# grizzly_bear.net
KiCad netlist of a schematic drawn in EAGLE
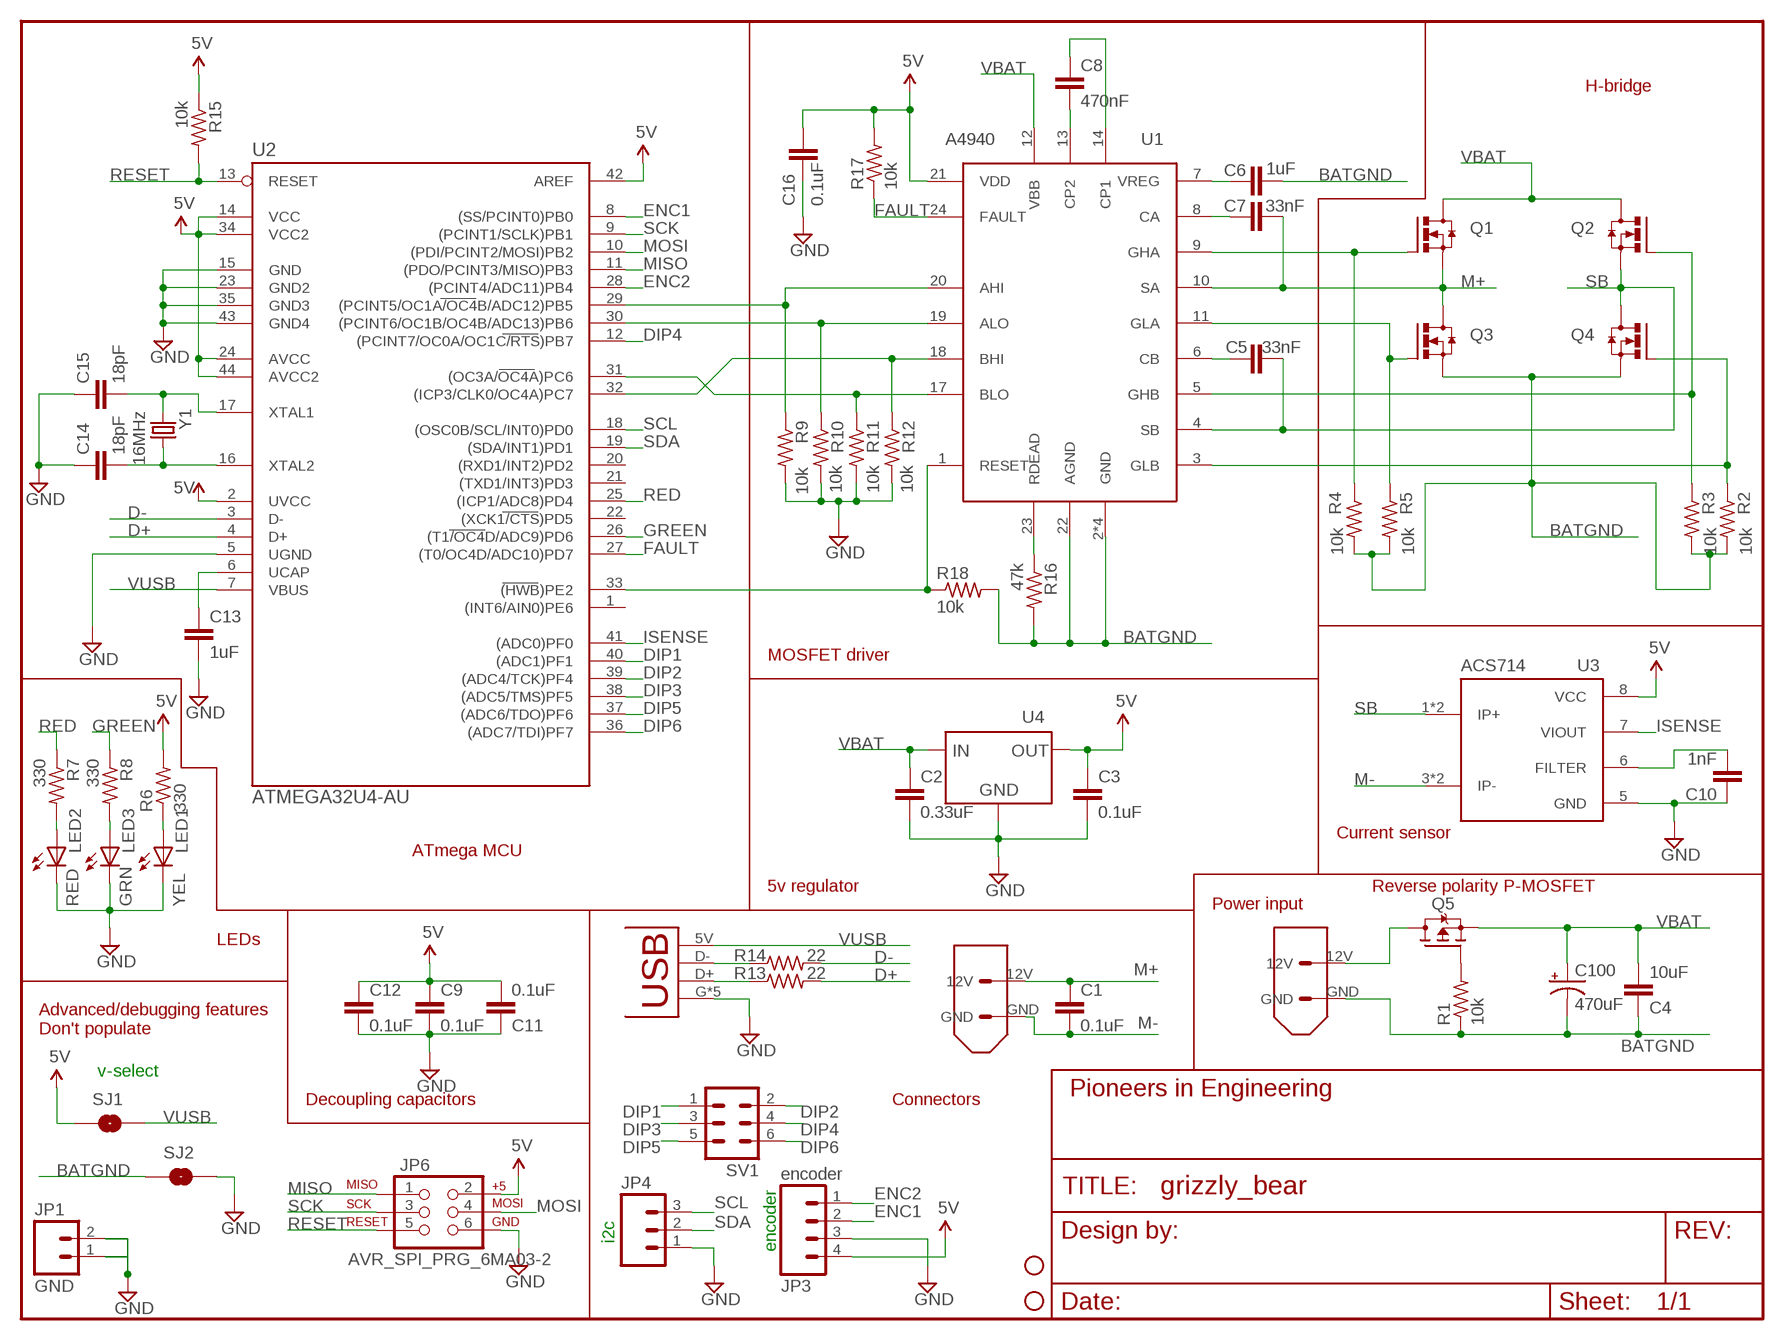
[diagram p0: schematic, sheet 1]

(export (version "E")
  (design (tool "Eeschema 10.0.6"))
  (components
    (comp (ref "C1")
      (value "0.1uF")
      (footprint "eagle-import:0603-CAP")
      (libsource (lib "eagle-import") (part "CAP0603-CAP"))
    )
    (comp (ref "C2")
      (value "0.33uF")
      (footprint "eagle-import:0603-CAP")
      (libsource (lib "eagle-import") (part "CAP0603-CAP"))
    )
    (comp (ref "C3")
      (value "0.1uF")
      (footprint "eagle-import:0603-CAP")
      (libsource (lib "eagle-import") (part "CAP0603-CAP"))
    )
    (comp (ref "C4")
      (value "10uF")
      (footprint "eagle-import:0603-CAP")
      (libsource (lib "eagle-import") (part "CAP0603-CAP"))
    )
    (comp (ref "C5")
      (value "33nF")
      (footprint "eagle-import:0603-CAP")
      (libsource (lib "eagle-import") (part "CAP0603-CAP"))
    )
    (comp (ref "C6")
      (value "1uF")
      (footprint "eagle-import:0603-CAP")
      (libsource (lib "eagle-import") (part "CAP0603-CAP"))
    )
    (comp (ref "C7")
      (value "33nF")
      (footprint "eagle-import:0603-CAP")
      (libsource (lib "eagle-import") (part "CAP0603-CAP"))
    )
    (comp (ref "C8")
      (value "470nF")
      (footprint "eagle-import:0603-CAP")
      (libsource (lib "eagle-import") (part "CAP0603-CAP"))
    )
    (comp (ref "C9")
      (value "0.1uF")
      (footprint "eagle-import:0603-CAP")
      (libsource (lib "eagle-import") (part "CAP0603-CAP"))
    )
    (comp (ref "C10")
      (value "1nF")
      (footprint "eagle-import:0603-CAP")
      (libsource (lib "eagle-import") (part "CAP0603-CAP"))
    )
    (comp (ref "C11")
      (value "0.1uF")
      (footprint "eagle-import:0603-CAP")
      (libsource (lib "eagle-import") (part "CAP0603-CAP"))
    )
    (comp (ref "C12")
      (value "0.1uF")
      (footprint "eagle-import:0603-CAP")
      (libsource (lib "eagle-import") (part "CAP0603-CAP"))
    )
    (comp (ref "C13")
      (value "1uF")
      (footprint "eagle-import:0603-CAP")
      (libsource (lib "eagle-import") (part "CAP0603-CAP"))
    )
    (comp (ref "C14")
      (value "18pF")
      (footprint "eagle-import:0603-CAP")
      (libsource (lib "eagle-import") (part "CAP0603-CAP"))
    )
    (comp (ref "C15")
      (value "18pF")
      (footprint "eagle-import:0603-CAP")
      (libsource (lib "eagle-import") (part "CAP0603-CAP"))
    )
    (comp (ref "C16")
      (value "0.1uF")
      (footprint "eagle-import:0603-CAP")
      (libsource (lib "eagle-import") (part "CAP0603-CAP"))
    )
    (comp (ref "C100")
      (value "470uF")
      (footprint "eagle-import:PANASONIC_G")
      (libsource (lib "eagle-import") (part "CAP_POLG"))
    )
    (comp (ref "JP1")
      (value "GND")
      (footprint "eagle-import:1X02")
      (libsource (lib "eagle-import") (part "M02PTH"))
    )
    (comp (ref "JP3")
      (value "encoder")
      (footprint "eagle-import:1X04-MTA")
      (fields (field (name "PARTNUMBER") "A1922-ND"))
      (libsource (lib "eagle-import") (part "M041X04-MTA"))
    )
    (comp (ref "JP4")
      (value "M031X03-MTA")
      (footprint "eagle-import:1X03-MTA")
      (fields (field (name "PARTNUMBER") "A19470-ND"))
      (libsource (lib "eagle-import") (part "M031X03-MTA"))
    )
    (comp (ref "JP6")
      (value "AVR_SPI_PRG_6MA03-2")
      (footprint "eagle-import:MA03-2")
      (libsource (lib "eagle-import") (part "AVR_SPI_PRG_6MA03-2"))
    )
    (comp (ref "LED1")
      (value "YEL")
      (footprint "eagle-import:LED-0805")
      (libsource (lib "eagle-import") (part "LED0805"))
    )
    (comp (ref "LED2")
      (value "RED")
      (footprint "eagle-import:LED-0805")
      (libsource (lib "eagle-import") (part "LED0805"))
    )
    (comp (ref "LED3")
      (value "GRN")
      (footprint "eagle-import:LED-0805")
      (libsource (lib "eagle-import") (part "LED0805"))
    )
    (comp (ref "Q1")
      (value "N-CHANNEL-MOSFET")
      (footprint "eagle-import:SOT669")
      (libsource (lib "eagle-import") (part "N-CHANNEL-MOSFET"))
    )
    (comp (ref "Q2")
      (value "N-CHANNEL-MOSFET")
      (footprint "eagle-import:SOT669")
      (libsource (lib "eagle-import") (part "N-CHANNEL-MOSFET"))
    )
    (comp (ref "Q3")
      (value "N-CHANNEL-MOSFET")
      (footprint "eagle-import:SOT669")
      (libsource (lib "eagle-import") (part "N-CHANNEL-MOSFET"))
    )
    (comp (ref "Q4")
      (value "N-CHANNEL-MOSFET")
      (footprint "eagle-import:SOT669")
      (libsource (lib "eagle-import") (part "N-CHANNEL-MOSFET"))
    )
    (comp (ref "Q5")
      (value "IPD90P03P4L")
      (footprint "eagle-import:TO252")
      (libsource (lib "eagle-import") (part "P-CHANNEL-MOSFETTO252"))
    )
    (comp (ref "R1")
      (value "10k")
      (footprint "eagle-import:R0603")
      (libsource (lib "eagle-import") (part "R-US_R0603"))
    )
    (comp (ref "R2")
      (value "10k")
      (footprint "eagle-import:R0603")
      (libsource (lib "eagle-import") (part "R-US_R0603"))
    )
    (comp (ref "R3")
      (value "10k")
      (footprint "eagle-import:R0603")
      (libsource (lib "eagle-import") (part "R-US_R0603"))
    )
    (comp (ref "R4")
      (value "10k")
      (footprint "eagle-import:R0603")
      (libsource (lib "eagle-import") (part "R-US_R0603"))
    )
    (comp (ref "R5")
      (value "10k")
      (footprint "eagle-import:R0603")
      (libsource (lib "eagle-import") (part "R-US_R0603"))
    )
    (comp (ref "R6")
      (value "330")
      (footprint "eagle-import:R0603")
      (libsource (lib "eagle-import") (part "R-US_R0603"))
    )
    (comp (ref "R7")
      (value "330")
      (footprint "eagle-import:R0603")
      (libsource (lib "eagle-import") (part "R-US_R0603"))
    )
    (comp (ref "R8")
      (value "330")
      (footprint "eagle-import:R0603")
      (libsource (lib "eagle-import") (part "R-US_R0603"))
    )
    (comp (ref "R9")
      (value "10k")
      (footprint "eagle-import:R0603")
      (libsource (lib "eagle-import") (part "R-US_R0603"))
    )
    (comp (ref "R10")
      (value "10k")
      (footprint "eagle-import:R0603")
      (libsource (lib "eagle-import") (part "R-US_R0603"))
    )
    (comp (ref "R11")
      (value "10k")
      (footprint "eagle-import:R0603")
      (libsource (lib "eagle-import") (part "R-US_R0603"))
    )
    (comp (ref "R12")
      (value "10k")
      (footprint "eagle-import:R0603")
      (libsource (lib "eagle-import") (part "R-US_R0603"))
    )
    (comp (ref "R13")
      (value "22")
      (footprint "eagle-import:R0603")
      (libsource (lib "eagle-import") (part "R-US_R0603"))
    )
    (comp (ref "R14")
      (value "22")
      (footprint "eagle-import:R0603")
      (libsource (lib "eagle-import") (part "R-US_R0603"))
    )
    (comp (ref "R15")
      (value "10k")
      (footprint "eagle-import:R0603")
      (libsource (lib "eagle-import") (part "R-US_R0603"))
    )
    (comp (ref "R16")
      (value "47k")
      (footprint "eagle-import:R0603")
      (libsource (lib "eagle-import") (part "R-US_R0603"))
    )
    (comp (ref "R17")
      (value "10k")
      (footprint "eagle-import:R0603")
      (libsource (lib "eagle-import") (part "R-US_R0603"))
    )
    (comp (ref "R18")
      (value "10k")
      (footprint "eagle-import:R0603")
      (libsource (lib "eagle-import") (part "R-US_R0603"))
    )
    (comp (ref "SJ1")
      (value "SOLDERJUMPERNO")
      (footprint "eagle-import:SJ_2S-NO")
      (libsource (lib "eagle-import") (part "SOLDERJUMPERNO"))
    )
    (comp (ref "SJ2")
      (value "SOLDERJUMPERNO")
      (footprint "eagle-import:SJ_2S-NO")
      (libsource (lib "eagle-import") (part "SOLDERJUMPERNO"))
    )
    (comp (ref "STANDOFF1")
      (value "STAND-OFF")
      (footprint "eagle-import:STAND-OFF")
      (libsource (lib "eagle-import") (part "STAND-OFF"))
    )
    (comp (ref "STANDOFF2")
      (value "STAND-OFF")
      (footprint "eagle-import:STAND-OFF")
      (libsource (lib "eagle-import") (part "STAND-OFF"))
    )
    (comp (ref "SV1")
      (value "MA03-2")
      (footprint "eagle-import:MA03-2")
      (libsource (lib "eagle-import") (part "MA03-2"))
    )
    (comp (ref "U$2")
      (value "USB-M26FTR")
      (footprint "eagle-import:USB-M26FTR")
      (libsource (lib "eagle-import") (part "USB-M26FTR"))
    )
    (comp (ref "U$18")
      (value "XT60CONNECTOR")
      (footprint "eagle-import:XT60CONNECTOR")
      (fields (field (name "PARTNUMBER") "PRT-10474 "))
      (libsource (lib "eagle-import") (part "XT60CONNECTOR"))
    )
    (comp (ref "U$19")
      (value "XT60CONNECTOR")
      (footprint "eagle-import:XT60CONNECTOR")
      (fields (field (name "PARTNUMBER") "PRT-10474 "))
      (libsource (lib "eagle-import") (part "XT60CONNECTOR"))
    )
    (comp (ref "U1")
      (value "A4940")
      (footprint "eagle-import:24-PIN_TSSOP")
      (libsource (lib "eagle-import") (part "A4940"))
    )
    (comp (ref "U2")
      (value "ATMEGA32U4-AU")
      (footprint "eagle-import:TQFP44")
      (libsource (lib "eagle-import") (part "ATMEGA32U4-AU"))
    )
    (comp (ref "U3")
      (value "ACS714")
      (footprint "eagle-import:8-PIN_SOIC")
      (libsource (lib "eagle-import") (part "ACS714"))
    )
    (comp (ref "U4")
      (value "UA78L00")
      (footprint "eagle-import:SOT-89-3")
      (libsource (lib "eagle-import") (part "UA78L00"))
    )
    (comp (ref "Y1")
      (value "16MHz")
      (footprint "eagle-import:HC49UP")
      (libsource (lib "eagle-import") (part "CRYSTALSMD"))
    )
  )
  (nets
    (net (code "1") (name "/BATGND") (class "Default")
      (node (ref "C100") (pin "-") (pinfunction "-_-") (pintype "passive"))
      (node (ref "C4") (pin "1") (pinfunction "1_1") (pintype "passive"))
      (node (ref "C6") (pin "2") (pinfunction "2_2") (pintype "passive"))
      (node (ref "Q3") (pin "1") (pinfunction "S_1") (pintype "passive"))
      (node (ref "Q3") (pin "2") (pinfunction "S_2") (pintype "passive"))
      (node (ref "Q3") (pin "3") (pinfunction "S_3") (pintype "passive"))
      (node (ref "Q4") (pin "1") (pinfunction "S_1") (pintype "passive"))
      (node (ref "Q4") (pin "2") (pinfunction "S_2") (pintype "passive"))
      (node (ref "Q4") (pin "3") (pinfunction "S_3") (pintype "passive"))
      (node (ref "R1") (pin "1") (pinfunction "1_1") (pintype "passive"))
      (node (ref "R16") (pin "2") (pinfunction "2_2") (pintype "passive"))
      (node (ref "R18") (pin "2") (pinfunction "2_2") (pintype "passive"))
      (node (ref "R2") (pin "2") (pinfunction "2_2") (pintype "passive"))
      (node (ref "R3") (pin "2") (pinfunction "2_2") (pintype "passive"))
      (node (ref "R4") (pin "2") (pinfunction "2_2") (pintype "passive"))
      (node (ref "R5") (pin "2") (pinfunction "2_2") (pintype "passive"))
      (node (ref "SJ2") (pin "1") (pinfunction "1_1") (pintype "passive"))
      (node (ref "U$18") (pin "GND") (pinfunction "GND_GND") (pintype "bidirectional"))
      (node (ref "U1") (pin "15") (pinfunction "GND_15") (pintype "bidirectional"))
      (node (ref "U1") (pin "16") (pinfunction "GND_16") (pintype "bidirectional"))
      (node (ref "U1") (pin "2") (pinfunction "GND_2") (pintype "bidirectional"))
      (node (ref "U1") (pin "22") (pinfunction "AGND_22") (pintype "bidirectional"))
      (node (ref "U1") (pin "PAD") (pinfunction "GND_PAD") (pintype "bidirectional"))
    )
    (net (code "2") (name "/D+") (class "Default")
      (node (ref "R13") (pin "2") (pinfunction "2_2") (pintype "passive"))
      (node (ref "U2") (pin "4") (pinfunction "D+_4") (pintype "bidirectional"))
    )
    (net (code "3") (name "/D-") (class "Default")
      (node (ref "R14") (pin "2") (pinfunction "2_2") (pintype "passive"))
      (node (ref "U2") (pin "3") (pinfunction "D-_3") (pintype "bidirectional"))
    )
    (net (code "4") (name "/DIP1") (class "Default")
      (node (ref "SV1") (pin "1") (pinfunction "1_1") (pintype "passive"))
      (node (ref "U2") (pin "40") (pinfunction "(ADC1)PF1_40") (pintype "bidirectional"))
    )
    (net (code "5") (name "/DIP2") (class "Default")
      (node (ref "SV1") (pin "2") (pinfunction "2_2") (pintype "passive"))
      (node (ref "U2") (pin "39") (pinfunction "(ADC4/TCK)PF4_39") (pintype "bidirectional"))
    )
    (net (code "6") (name "/DIP3") (class "Default")
      (node (ref "SV1") (pin "3") (pinfunction "3_3") (pintype "passive"))
      (node (ref "U2") (pin "38") (pinfunction "(ADC5/TMS)PF5_38") (pintype "bidirectional"))
    )
    (net (code "7") (name "/DIP4") (class "Default")
      (node (ref "SV1") (pin "4") (pinfunction "4_4") (pintype "passive"))
      (node (ref "U2") (pin "12") (pinfunction "(PCINT7/OC0A/OC1C/RTS)PB7_12") (pintype "bidirectional"))
    )
    (net (code "8") (name "/DIP5") (class "Default")
      (node (ref "SV1") (pin "5") (pinfunction "5_5") (pintype "passive"))
      (node (ref "U2") (pin "37") (pinfunction "(ADC6/TDO)PF6_37") (pintype "bidirectional"))
    )
    (net (code "9") (name "/DIP6") (class "Default")
      (node (ref "SV1") (pin "6") (pinfunction "6_6") (pintype "passive"))
      (node (ref "U2") (pin "36") (pinfunction "(ADC7/TDI)PF7_36") (pintype "bidirectional"))
    )
    (net (code "10") (name "/ENC1") (class "Default")
      (node (ref "JP3") (pin "2") (pinfunction "2_2") (pintype "passive"))
      (node (ref "U2") (pin "8") (pinfunction "(SS/PCINT0)PB0_8") (pintype "bidirectional"))
    )
    (net (code "11") (name "/ENC2") (class "Default")
      (node (ref "JP3") (pin "1") (pinfunction "1_1") (pintype "passive"))
      (node (ref "U2") (pin "28") (pinfunction "(PCINT4/ADC11)PB4_28") (pintype "bidirectional"))
    )
    (net (code "12") (name "/FAULT") (class "Default")
      (node (ref "R17") (pin "1") (pinfunction "1_1") (pintype "passive"))
      (node (ref "U1") (pin "24") (pinfunction "FAULT_24") (pintype "bidirectional"))
      (node (ref "U2") (pin "27") (pinfunction "(T0/OC4D/ADC10)PD7_27") (pintype "bidirectional"))
    )
    (net (code "13") (name "/GREEN") (class "Default")
      (node (ref "R8") (pin "1") (pinfunction "1_1") (pintype "passive"))
      (node (ref "U2") (pin "26") (pinfunction "(T1/OC4D/ADC9)PD6_26") (pintype "bidirectional"))
    )
    (net (code "14") (name "/ISENSE") (class "Default")
      (node (ref "U2") (pin "41") (pinfunction "(ADC0)PF0_41") (pintype "bidirectional"))
      (node (ref "U3") (pin "7") (pinfunction "VIOUT_7") (pintype "bidirectional"))
    )
    (net (code "15") (name "/M+") (class "Default")
      (node (ref "C1") (pin "1") (pinfunction "1_1") (pintype "passive"))
      (node (ref "C7") (pin "2") (pinfunction "2_2") (pintype "passive"))
      (node (ref "Q1") (pin "1") (pinfunction "S_1") (pintype "passive"))
      (node (ref "Q1") (pin "2") (pinfunction "S_2") (pintype "passive"))
      (node (ref "Q1") (pin "3") (pinfunction "S_3") (pintype "passive"))
      (node (ref "Q3") (pin "MB") (pinfunction "D_MB") (pintype "passive"))
      (node (ref "U$19") (pin "12V") (pinfunction "12V_12V") (pintype "bidirectional"))
      (node (ref "U1") (pin "10") (pinfunction "SA_10") (pintype "bidirectional"))
    )
    (net (code "16") (name "/M-") (class "Default")
      (node (ref "C1") (pin "2") (pinfunction "2_2") (pintype "passive"))
      (node (ref "U$19") (pin "GND") (pinfunction "GND_GND") (pintype "bidirectional"))
      (node (ref "U3") (pin "3") (pinfunction "IP-_3") (pintype "bidirectional"))
      (node (ref "U3") (pin "4") (pinfunction "IP-_4") (pintype "bidirectional"))
    )
    (net (code "17") (name "/MISO") (class "Default")
      (node (ref "JP6") (pin "1") (pinfunction "1_1") (pintype "passive"))
      (node (ref "U2") (pin "11") (pinfunction "(PDO/PCINT3/MISO)PB3_11") (pintype "bidirectional"))
    )
    (net (code "18") (name "/MOSI") (class "Default")
      (node (ref "JP6") (pin "4") (pinfunction "4_4") (pintype "passive"))
      (node (ref "U2") (pin "10") (pinfunction "(PDI/PCINT2/MOSI)PB2_10") (pintype "bidirectional"))
    )
    (net (code "19") (name "/RED") (class "Default")
      (node (ref "R7") (pin "1") (pinfunction "1_1") (pintype "passive"))
      (node (ref "U2") (pin "25") (pinfunction "(ICP1/ADC8)PD4_25") (pintype "bidirectional"))
    )
    (net (code "20") (name "/RESET") (class "Default")
      (node (ref "JP6") (pin "5") (pinfunction "5_5") (pintype "passive"))
      (node (ref "R15") (pin "2") (pinfunction "2_2") (pintype "passive"))
      (node (ref "U2") (pin "13") (pinfunction "RESET_13") (pintype "bidirectional"))
    )
    (net (code "21") (name "/SB") (class "Default")
      (node (ref "C5") (pin "1") (pinfunction "1_1") (pintype "passive"))
      (node (ref "Q2") (pin "1") (pinfunction "S_1") (pintype "passive"))
      (node (ref "Q2") (pin "2") (pinfunction "S_2") (pintype "passive"))
      (node (ref "Q2") (pin "3") (pinfunction "S_3") (pintype "passive"))
      (node (ref "Q4") (pin "MB") (pinfunction "D_MB") (pintype "passive"))
      (node (ref "U1") (pin "4") (pinfunction "SB_4") (pintype "bidirectional"))
      (node (ref "U3") (pin "1") (pinfunction "IP+_1") (pintype "bidirectional"))
      (node (ref "U3") (pin "2") (pinfunction "IP+_2") (pintype "bidirectional"))
    )
    (net (code "22") (name "/SCK") (class "Default")
      (node (ref "JP6") (pin "3") (pinfunction "3_3") (pintype "passive"))
      (node (ref "U2") (pin "9") (pinfunction "(PCINT1/SCLK)PB1_9") (pintype "bidirectional"))
    )
    (net (code "23") (name "/SCL") (class "Default")
      (node (ref "JP4") (pin "3") (pinfunction "3_3") (pintype "passive"))
      (node (ref "U2") (pin "18") (pinfunction "(OSC0B/SCL/INT0)PD0_18") (pintype "bidirectional"))
    )
    (net (code "24") (name "/SDA") (class "Default")
      (node (ref "JP4") (pin "2") (pinfunction "2_2") (pintype "passive"))
      (node (ref "U2") (pin "19") (pinfunction "(SDA/INT1)PD1_19") (pintype "bidirectional"))
    )
    (net (code "25") (name "/VBAT") (class "Default")
      (node (ref "C100") (pin "+") (pinfunction "+_+") (pintype "passive"))
      (node (ref "C2") (pin "1") (pinfunction "1_1") (pintype "passive"))
      (node (ref "C4") (pin "2") (pinfunction "2_2") (pintype "passive"))
      (node (ref "Q1") (pin "MB") (pinfunction "D_MB") (pintype "passive"))
      (node (ref "Q2") (pin "MB") (pinfunction "D_MB") (pintype "passive"))
      (node (ref "Q5") (pin "2") (pinfunction "S_2") (pintype "passive"))
      (node (ref "U1") (pin "12") (pinfunction "VBB_12") (pintype "bidirectional"))
      (node (ref "U4") (pin "INPUT") (pinfunction "IN_INPUT") (pintype "bidirectional"))
    )
    (net (code "26") (name "/VUSB") (class "Default")
      (node (ref "SJ1") (pin "2") (pinfunction "2_2") (pintype "passive"))
      (node (ref "U$2") (pin "5V") (pinfunction "5V_5V") (pintype "bidirectional"))
      (node (ref "U2") (pin "7") (pinfunction "VBUS_7") (pintype "bidirectional"))
    )
    (net (code "27") (name "5V") (class "Default")
      (node (ref "C11") (pin "2") (pinfunction "2_2") (pintype "passive"))
      (node (ref "C12") (pin "1") (pinfunction "1_1") (pintype "passive"))
      (node (ref "C16") (pin "1") (pinfunction "1_1") (pintype "passive"))
      (node (ref "C3") (pin "1") (pinfunction "1_1") (pintype "passive"))
      (node (ref "C9") (pin "1") (pinfunction "1_1") (pintype "passive"))
      (node (ref "JP3") (pin "4") (pinfunction "4_4") (pintype "passive"))
      (node (ref "JP6") (pin "2") (pinfunction "2_2") (pintype "passive"))
      (node (ref "R15") (pin "1") (pinfunction "1_1") (pintype "passive"))
      (node (ref "R17") (pin "2") (pinfunction "2_2") (pintype "passive"))
      (node (ref "R6") (pin "2") (pinfunction "2_2") (pintype "passive"))
      (node (ref "SJ1") (pin "1") (pinfunction "1_1") (pintype "passive"))
      (node (ref "U1") (pin "21") (pinfunction "VDD_21") (pintype "bidirectional"))
      (node (ref "U2") (pin "14") (pinfunction "VCC_14") (pintype "bidirectional"))
      (node (ref "U2") (pin "2") (pinfunction "UVCC_2") (pintype "bidirectional"))
      (node (ref "U2") (pin "24") (pinfunction "AVCC_24") (pintype "bidirectional"))
      (node (ref "U2") (pin "34") (pinfunction "VCC2_34") (pintype "bidirectional"))
      (node (ref "U2") (pin "42") (pinfunction "AREF_42") (pintype "bidirectional"))
      (node (ref "U2") (pin "44") (pinfunction "AVCC2_44") (pintype "bidirectional"))
      (node (ref "U3") (pin "8") (pinfunction "VCC_8") (pintype "bidirectional"))
      (node (ref "U4") (pin "OUTPUT") (pinfunction "OUT_OUTPUT") (pintype "bidirectional"))
    )
    (net (code "28") (name "GND") (class "Default")
      (node (ref "C10") (pin "1") (pinfunction "1_1") (pintype "passive"))
      (node (ref "C11") (pin "1") (pinfunction "1_1") (pintype "passive"))
      (node (ref "C12") (pin "2") (pinfunction "2_2") (pintype "passive"))
      (node (ref "C13") (pin "2") (pinfunction "2_2") (pintype "passive"))
      (node (ref "C14") (pin "1") (pinfunction "1_1") (pintype "passive"))
      (node (ref "C15") (pin "1") (pinfunction "1_1") (pintype "passive"))
      (node (ref "C16") (pin "2") (pinfunction "2_2") (pintype "passive"))
      (node (ref "C2") (pin "2") (pinfunction "2_2") (pintype "passive"))
      (node (ref "C3") (pin "2") (pinfunction "2_2") (pintype "passive"))
      (node (ref "C9") (pin "2") (pinfunction "2_2") (pintype "passive"))
      (node (ref "JP1") (pin "1") (pinfunction "1_1") (pintype "passive"))
      (node (ref "JP1") (pin "2") (pinfunction "2_2") (pintype "passive"))
      (node (ref "JP3") (pin "3") (pinfunction "3_3") (pintype "passive"))
      (node (ref "JP4") (pin "1") (pinfunction "1_1") (pintype "passive"))
      (node (ref "JP6") (pin "6") (pinfunction "6_6") (pintype "passive"))
      (node (ref "LED1") (pin "C") (pinfunction "C_C") (pintype "passive"))
      (node (ref "LED2") (pin "C") (pinfunction "C_C") (pintype "passive"))
      (node (ref "LED3") (pin "C") (pinfunction "C_C") (pintype "passive"))
      (node (ref "R10") (pin "2") (pinfunction "2_2") (pintype "passive"))
      (node (ref "R11") (pin "2") (pinfunction "2_2") (pintype "passive"))
      (node (ref "R12") (pin "2") (pinfunction "2_2") (pintype "passive"))
      (node (ref "R9") (pin "2") (pinfunction "2_2") (pintype "passive"))
      (node (ref "SJ2") (pin "2") (pinfunction "2_2") (pintype "passive"))
      (node (ref "U$2") (pin "G") (pinfunction "G_G") (pintype "bidirectional"))
      (node (ref "U$2") (pin "S1") (pinfunction "G_S1") (pintype "bidirectional"))
      (node (ref "U$2") (pin "S2") (pinfunction "G_S2") (pintype "bidirectional"))
      (node (ref "U$2") (pin "S3") (pinfunction "G_S3") (pintype "bidirectional"))
      (node (ref "U$2") (pin "S4") (pinfunction "G_S4") (pintype "bidirectional"))
      (node (ref "U2") (pin "15") (pinfunction "GND_15") (pintype "bidirectional"))
      (node (ref "U2") (pin "23") (pinfunction "GND2_23") (pintype "bidirectional"))
      (node (ref "U2") (pin "35") (pinfunction "GND3_35") (pintype "bidirectional"))
      (node (ref "U2") (pin "43") (pinfunction "GND4_43") (pintype "bidirectional"))
      (node (ref "U2") (pin "5") (pinfunction "UGND_5") (pintype "bidirectional"))
      (node (ref "U3") (pin "5") (pinfunction "GND_5") (pintype "bidirectional"))
      (node (ref "U4") (pin "COMMON") (pinfunction "GND_COMMON") (pintype "bidirectional"))
    )
    (net (code "29") (name "Net-(LED1-PadA)") (class "Default")
      (node (ref "LED1") (pin "A") (pinfunction "A_A") (pintype "passive"))
      (node (ref "R6") (pin "1") (pinfunction "1_1") (pintype "passive"))
    )
    (net (code "30") (name "Net-(LED2-PadA)") (class "Default")
      (node (ref "LED2") (pin "A") (pinfunction "A_A") (pintype "passive"))
      (node (ref "R7") (pin "2") (pinfunction "2_2") (pintype "passive"))
    )
    (net (code "31") (name "Net-(LED3-PadA)") (class "Default")
      (node (ref "LED3") (pin "A") (pinfunction "A_A") (pintype "passive"))
      (node (ref "R8") (pin "2") (pinfunction "2_2") (pintype "passive"))
    )
    (net (code "32") (name "Net-(Q1-G)") (class "Default")
      (node (ref "Q1") (pin "4") (pinfunction "G_4") (pintype "passive"))
      (node (ref "R4") (pin "1") (pinfunction "1_1") (pintype "passive"))
      (node (ref "U1") (pin "9") (pinfunction "GHA_9") (pintype "bidirectional"))
    )
    (net (code "33") (name "Net-(Q2-G)") (class "Default")
      (node (ref "Q2") (pin "4") (pinfunction "G_4") (pintype "passive"))
      (node (ref "R3") (pin "1") (pinfunction "1_1") (pintype "passive"))
      (node (ref "U1") (pin "5") (pinfunction "GHB_5") (pintype "bidirectional"))
    )
    (net (code "34") (name "Net-(Q3-G)") (class "Default")
      (node (ref "Q3") (pin "4") (pinfunction "G_4") (pintype "passive"))
      (node (ref "R5") (pin "1") (pinfunction "1_1") (pintype "passive"))
      (node (ref "U1") (pin "11") (pinfunction "GLA_11") (pintype "bidirectional"))
    )
    (net (code "35") (name "Net-(Q4-G)") (class "Default")
      (node (ref "Q4") (pin "4") (pinfunction "G_4") (pintype "passive"))
      (node (ref "R2") (pin "1") (pinfunction "1_1") (pintype "passive"))
      (node (ref "U1") (pin "3") (pinfunction "GLB_3") (pintype "bidirectional"))
    )
    (net (code "36") (name "Net-(Q5-D)") (class "Default")
      (node (ref "Q5") (pin "3") (pinfunction "D_3") (pintype "passive"))
      (node (ref "U$18") (pin "12V") (pinfunction "12V_12V") (pintype "bidirectional"))
    )
    (net (code "37") (name "Net-(Q5-G)") (class "Default")
      (node (ref "Q5") (pin "1") (pinfunction "G_1") (pintype "passive"))
      (node (ref "R1") (pin "2") (pinfunction "2_2") (pintype "passive"))
    )
    (net (code "38") (name "Net-(R13-Pad1)") (class "Default")
      (node (ref "R13") (pin "1") (pinfunction "1_1") (pintype "passive"))
      (node (ref "U$2") (pin "D+") (pinfunction "D+_D+") (pintype "bidirectional"))
    )
    (net (code "39") (name "Net-(R14-Pad1)") (class "Default")
      (node (ref "R14") (pin "1") (pinfunction "1_1") (pintype "passive"))
      (node (ref "U$2") (pin "D-") (pinfunction "D-_D-") (pintype "bidirectional"))
    )
    (net (code "40") (name "Net-(U1-AHI)") (class "Default")
      (node (ref "R9") (pin "1") (pinfunction "1_1") (pintype "passive"))
      (node (ref "U1") (pin "20") (pinfunction "AHI_20") (pintype "bidirectional"))
      (node (ref "U2") (pin "29") (pinfunction "(PCINT5/OC1A/OC4B/ADC12)PB5_29") (pintype "bidirectional"))
    )
    (net (code "41") (name "Net-(U1-ALO)") (class "Default")
      (node (ref "R10") (pin "1") (pinfunction "1_1") (pintype "passive"))
      (node (ref "U1") (pin "19") (pinfunction "ALO_19") (pintype "bidirectional"))
      (node (ref "U2") (pin "30") (pinfunction "(PCINT6/OC1B/OC4B/ADC13)PB6_30") (pintype "bidirectional"))
    )
    (net (code "42") (name "Net-(U1-BHI)") (class "Default")
      (node (ref "R12") (pin "1") (pinfunction "1_1") (pintype "passive"))
      (node (ref "U1") (pin "18") (pinfunction "BHI_18") (pintype "bidirectional"))
      (node (ref "U2") (pin "32") (pinfunction "(ICP3/CLK0/OC4A)PC7_32") (pintype "bidirectional"))
    )
    (net (code "43") (name "Net-(U1-BLO)") (class "Default")
      (node (ref "R11") (pin "1") (pinfunction "1_1") (pintype "passive"))
      (node (ref "U1") (pin "17") (pinfunction "BLO_17") (pintype "bidirectional"))
      (node (ref "U2") (pin "31") (pinfunction "(OC3A/OC4A)PC6_31") (pintype "bidirectional"))
    )
    (net (code "44") (name "Net-(U1-CA)") (class "Default")
      (node (ref "C7") (pin "1") (pinfunction "1_1") (pintype "passive"))
      (node (ref "U1") (pin "8") (pinfunction "CA_8") (pintype "bidirectional"))
    )
    (net (code "45") (name "Net-(U1-CB)") (class "Default")
      (node (ref "C5") (pin "2") (pinfunction "2_2") (pintype "passive"))
      (node (ref "U1") (pin "6") (pinfunction "CB_6") (pintype "bidirectional"))
    )
    (net (code "46") (name "Net-(U1-CP1)") (class "Default")
      (node (ref "C8") (pin "1") (pinfunction "1_1") (pintype "passive"))
      (node (ref "U1") (pin "14") (pinfunction "CP1_14") (pintype "bidirectional"))
    )
    (net (code "47") (name "Net-(U1-CP2)") (class "Default")
      (node (ref "C8") (pin "2") (pinfunction "2_2") (pintype "passive"))
      (node (ref "U1") (pin "13") (pinfunction "CP2_13") (pintype "bidirectional"))
    )
    (net (code "48") (name "Net-(U1-RDEAD)") (class "Default")
      (node (ref "R16") (pin "1") (pinfunction "1_1") (pintype "passive"))
      (node (ref "U1") (pin "23") (pinfunction "RDEAD_23") (pintype "bidirectional"))
    )
    (net (code "49") (name "Net-(U1-RESET)") (class "Default")
      (node (ref "R18") (pin "1") (pinfunction "1_1") (pintype "passive"))
      (node (ref "U1") (pin "1") (pinfunction "RESET_1") (pintype "bidirectional"))
      (node (ref "U2") (pin "33") (pinfunction "(HWB)PE2_33") (pintype "bidirectional"))
    )
    (net (code "50") (name "Net-(U1-VREG)") (class "Default")
      (node (ref "C6") (pin "1") (pinfunction "1_1") (pintype "passive"))
      (node (ref "U1") (pin "7") (pinfunction "VREG_7") (pintype "bidirectional"))
    )
    (net (code "51") (name "Net-(U2-UCAP)") (class "Default")
      (node (ref "C13") (pin "1") (pinfunction "1_1") (pintype "passive"))
      (node (ref "U2") (pin "6") (pinfunction "UCAP_6") (pintype "bidirectional"))
    )
    (net (code "52") (name "Net-(U2-XTAL1)") (class "Default")
      (node (ref "C15") (pin "2") (pinfunction "2_2") (pintype "passive"))
      (node (ref "U2") (pin "17") (pinfunction "XTAL1_17") (pintype "bidirectional"))
      (node (ref "Y1") (pin "2") (pinfunction "2_2") (pintype "passive"))
    )
    (net (code "53") (name "Net-(U2-XTAL2)") (class "Default")
      (node (ref "C14") (pin "2") (pinfunction "2_2") (pintype "passive"))
      (node (ref "U2") (pin "16") (pinfunction "XTAL2_16") (pintype "bidirectional"))
      (node (ref "Y1") (pin "1") (pinfunction "1_1") (pintype "passive"))
    )
    (net (code "54") (name "Net-(U3-FILTER)") (class "Default")
      (node (ref "C10") (pin "2") (pinfunction "2_2") (pintype "passive"))
      (node (ref "U3") (pin "6") (pinfunction "FILTER_6") (pintype "bidirectional"))
    )
    (net (code "55") (name "unconnected-(U2-(INT6{slash}AIN0)PE6-Pad1)") (class "Default")
      (node (ref "U2") (pin "1") (pinfunction "(INT6/AIN0)PE6_1") (pintype "bidirectional"))
    )
    (net (code "56") (name "unconnected-(U2-(RXD1{slash}INT2)PD2-Pad20)") (class "Default")
      (node (ref "U2") (pin "20") (pinfunction "(RXD1/INT2)PD2_20") (pintype "bidirectional"))
    )
    (net (code "57") (name "unconnected-(U2-(TXD1{slash}INT3)PD3-Pad21)") (class "Default")
      (node (ref "U2") (pin "21") (pinfunction "(TXD1/INT3)PD3_21") (pintype "bidirectional"))
    )
    (net (code "58") (name "unconnected-(U2-(XCK1{slash}CTS)PD5-Pad22)") (class "Default")
      (node (ref "U2") (pin "22") (pinfunction "(XCK1/CTS)PD5_22") (pintype "bidirectional"))
    )
  )
)
